# Main_and_Tower.net
KiCad netlist of a schematic drawn in EAGLE
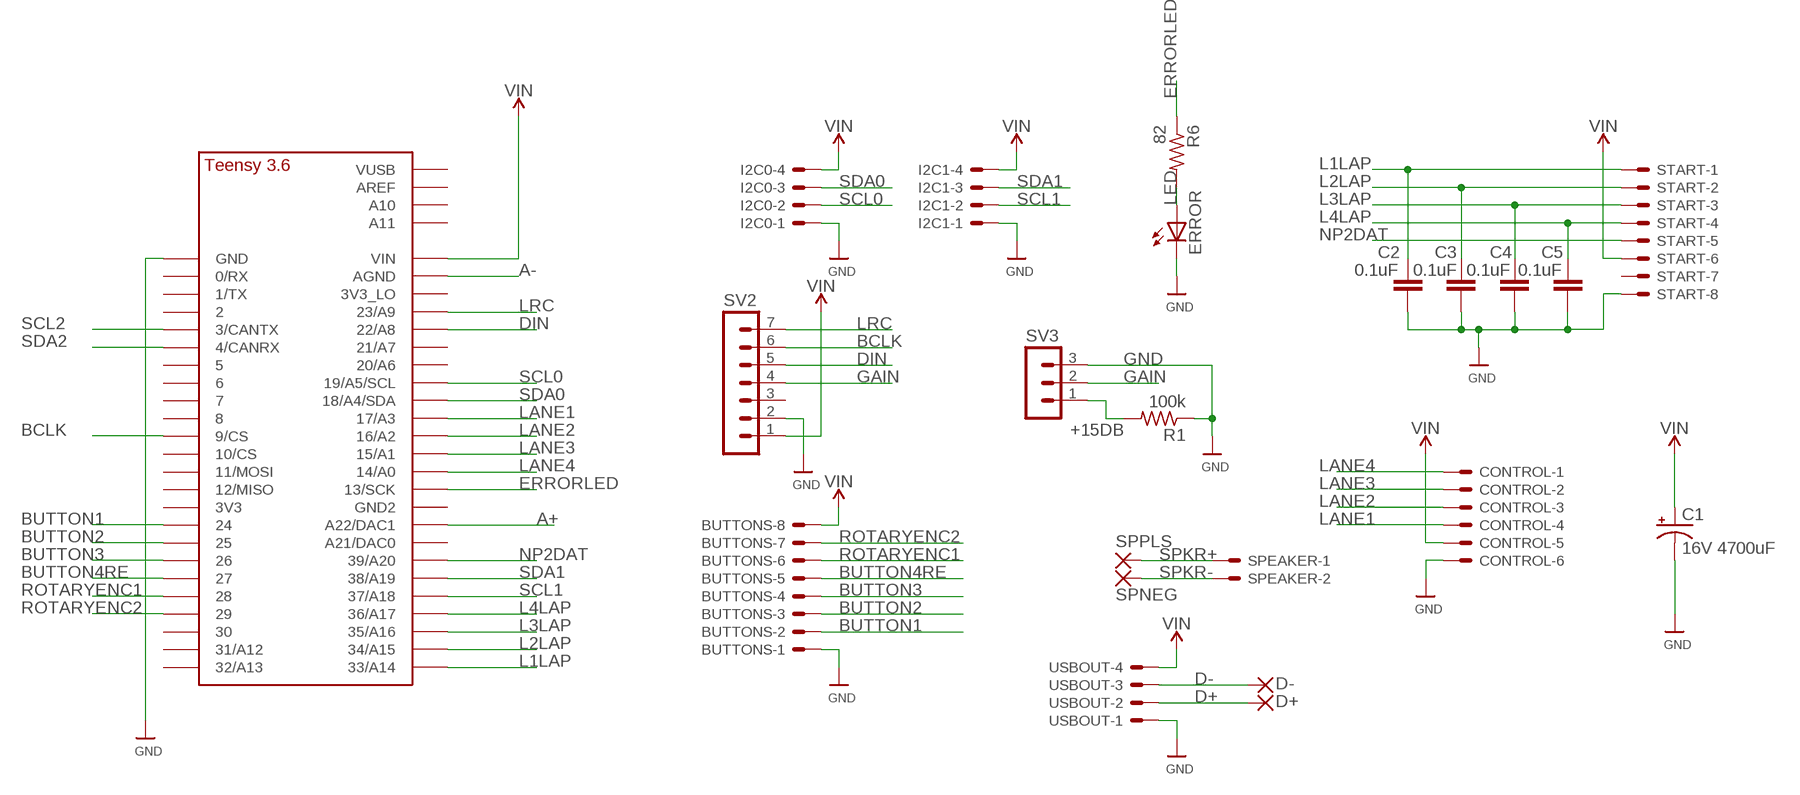
[diagram p0: schematic, sheet 1]

(export (version "E")
  (design (tool "Eeschema 10.0.6"))
  (components
    (comp (ref "BUTTONS")
      (value "KK-156-8")
      (footprint "eagle-import:KK-156-8")
      (fields (field (name "MF") "MOLEX"))
      (libsource (lib "eagle-import") (part "KK-156-8"))
    )
    (comp (ref "C1")
      (value "16V 4700uF")
      (footprint "eagle-import:CAPPRD550W110D1250H2500B")
      (libsource (lib "eagle-import") (part "C-POL-USRADIAL-25MM-DIA_"))
    )
    (comp (ref "C2")
      (value "0.1uF")
      (footprint "eagle-import:CAPC3216X135")
      (libsource (lib "eagle-import") (part "CCHIP-1206(3216-METRIC)_"))
    )
    (comp (ref "C3")
      (value "0.1uF")
      (footprint "eagle-import:CAPC3216X135")
      (libsource (lib "eagle-import") (part "CCHIP-1206(3216-METRIC)_"))
    )
    (comp (ref "C4")
      (value "0.1uF")
      (footprint "eagle-import:CAPC3216X135")
      (libsource (lib "eagle-import") (part "CCHIP-1206(3216-METRIC)_"))
    )
    (comp (ref "C5")
      (value "0.1uF")
      (footprint "eagle-import:CAPC3216X135")
      (libsource (lib "eagle-import") (part "CCHIP-1206(3216-METRIC)_"))
    )
    (comp (ref "CONTROL")
      (value "KK-156-6")
      (footprint "eagle-import:KK-156-6")
      (fields (field (name "MF") "MOLEX"))
      (libsource (lib "eagle-import") (part "KK-156-6"))
    )
    (comp (ref "D+")
      (value "1,6/0,8")
      (footprint "eagle-import:1,6_0,8")
      (libsource (lib "eagle-import") (part "1,6/0,8"))
    )
    (comp (ref "D-")
      (value "1,6/0,8")
      (footprint "eagle-import:1,6_0,8")
      (libsource (lib "eagle-import") (part "1,6/0,8"))
    )
    (comp (ref "ERROR")
      (value "LEDCHIPLED_1206")
      (footprint "eagle-import:CHIPLED_1206")
      (libsource (lib "eagle-import") (part "LEDCHIPLED_1206"))
    )
    (comp (ref "I2C0")
      (value "KK-156-4")
      (footprint "eagle-import:KK-156-4")
      (fields (field (name "MF") "MOLEX"))
      (libsource (lib "eagle-import") (part "KK-156-4"))
    )
    (comp (ref "I2C1")
      (value "KK-156-4")
      (footprint "eagle-import:KK-156-4")
      (fields (field (name "MF") "MOLEX"))
      (libsource (lib "eagle-import") (part "KK-156-4"))
    )
    (comp (ref "R1")
      (value "100k")
      (footprint "eagle-import:M1206")
      (libsource (lib "eagle-import") (part "R-US_M1206"))
    )
    (comp (ref "R6")
      (value "82")
      (footprint "eagle-import:M1206")
      (libsource (lib "eagle-import") (part "R-US_M1206"))
    )
    (comp (ref "SPEAKER")
      (value "KK-156-2")
      (footprint "eagle-import:KK-156-2")
      (fields (field (name "MF") "MOLEX"))
      (libsource (lib "eagle-import") (part "KK-156-2"))
    )
    (comp (ref "SPNEG")
      (value "2,54/1,1")
      (footprint "eagle-import:2,54_1,1")
      (libsource (lib "eagle-import") (part "2,54/1,1"))
    )
    (comp (ref "SPPLS")
      (value "2,54/1,1")
      (footprint "eagle-import:2,54_1,1")
      (libsource (lib "eagle-import") (part "2,54/1,1"))
    )
    (comp (ref "START")
      (value "KK-156-8")
      (footprint "eagle-import:KK-156-8")
      (fields (field (name "MF") "MOLEX"))
      (libsource (lib "eagle-import") (part "KK-156-8"))
    )
    (comp (ref "SV2")
      (value "MA07-1")
      (footprint "eagle-import:MA07-1")
      (libsource (lib "eagle-import") (part "MA07-1"))
    )
    (comp (ref "SV3")
      (value "MA03-1")
      (footprint "eagle-import:MA03-1")
      (libsource (lib "eagle-import") (part "MA03-1"))
    )
    (comp (ref "U$1")
      (value "TEENSY_3.5/3.6_BASIC")
      (footprint "eagle-import:TEENSY_3.5_3.6_BASIC")
      (libsource (lib "eagle-import") (part "TEENSY_3.5/3.6_BASIC"))
    )
    (comp (ref "USBOUT")
      (value "KK-156-4")
      (footprint "eagle-import:KK-156-4")
      (fields (field (name "MF") "MOLEX"))
      (libsource (lib "eagle-import") (part "KK-156-4"))
    )
  )
  (nets
    (net (code "1") (name "/+15DB") (class "Default")
      (node (ref "R1") (pin "2") (pinfunction "2_2") (pintype "passive"))
      (node (ref "SV3") (pin "1") (pinfunction "1_1") (pintype "passive"))
    )
    (net (code "2") (name "/A+") (class "Default")
      (node (ref "U$1") (pin "A22/DAC1") (pinfunction "A22/DAC1_A22/DAC1") (pintype "bidirectional"))
    )
    (net (code "3") (name "/A-") (class "Default")
      (node (ref "U$1") (pin "AGND") (pinfunction "AGND_AGND") (pintype "bidirectional"))
    )
    (net (code "4") (name "/BCLK") (class "Default")
      (node (ref "SV2") (pin "6") (pinfunction "6_6") (pintype "passive"))
      (node (ref "U$1") (pin "9/CS") (pinfunction "9/CS_9/CS") (pintype "bidirectional"))
    )
    (net (code "5") (name "/BUTTON1") (class "Default")
      (node (ref "BUTTONS") (pin "2") (pinfunction "S_2") (pintype "passive"))
      (node (ref "U$1") (pin "24") (pinfunction "24_24") (pintype "bidirectional"))
    )
    (net (code "6") (name "/BUTTON2") (class "Default")
      (node (ref "BUTTONS") (pin "3") (pinfunction "S_3") (pintype "passive"))
      (node (ref "U$1") (pin "25") (pinfunction "25_25") (pintype "bidirectional"))
    )
    (net (code "7") (name "/BUTTON3") (class "Default")
      (node (ref "BUTTONS") (pin "4") (pinfunction "S_4") (pintype "passive"))
      (node (ref "U$1") (pin "26") (pinfunction "26_26") (pintype "bidirectional"))
    )
    (net (code "8") (name "/BUTTON4RE") (class "Default")
      (node (ref "BUTTONS") (pin "5") (pinfunction "S_5") (pintype "passive"))
      (node (ref "U$1") (pin "27") (pinfunction "27_27") (pintype "bidirectional"))
    )
    (net (code "9") (name "/D+") (class "Default")
      (node (ref "D+") (pin "1") (pinfunction "P_1") (pintype "passive"))
      (node (ref "USBOUT") (pin "2") (pinfunction "S_2") (pintype "passive"))
    )
    (net (code "10") (name "/D-") (class "Default")
      (node (ref "D-") (pin "1") (pinfunction "P_1") (pintype "passive"))
      (node (ref "USBOUT") (pin "3") (pinfunction "S_3") (pintype "passive"))
    )
    (net (code "11") (name "/DIN") (class "Default")
      (node (ref "SV2") (pin "5") (pinfunction "5_5") (pintype "passive"))
      (node (ref "U$1") (pin "22/A8") (pinfunction "22/A8_22/A8") (pintype "bidirectional"))
    )
    (net (code "12") (name "/ERRORLED") (class "Default")
      (node (ref "R6") (pin "1") (pinfunction "1_1") (pintype "passive"))
      (node (ref "U$1") (pin "13/SCK") (pinfunction "13/SCK_13/SCK") (pintype "bidirectional"))
    )
    (net (code "13") (name "/GAIN") (class "Default")
      (node (ref "SV2") (pin "4") (pinfunction "4_4") (pintype "passive"))
      (node (ref "SV3") (pin "2") (pinfunction "2_2") (pintype "passive"))
    )
    (net (code "14") (name "/L1LAP") (class "Default")
      (node (ref "C2") (pin "1") (pinfunction "1_1") (pintype "passive"))
      (node (ref "START") (pin "1") (pinfunction "S_1") (pintype "passive"))
      (node (ref "U$1") (pin "33/A14") (pinfunction "33/A14_33/A14") (pintype "bidirectional"))
    )
    (net (code "15") (name "/L2LAP") (class "Default")
      (node (ref "C3") (pin "1") (pinfunction "1_1") (pintype "passive"))
      (node (ref "START") (pin "2") (pinfunction "S_2") (pintype "passive"))
      (node (ref "U$1") (pin "34/A15") (pinfunction "34/A15_34/A15") (pintype "bidirectional"))
    )
    (net (code "16") (name "/L3LAP") (class "Default")
      (node (ref "C4") (pin "1") (pinfunction "1_1") (pintype "passive"))
      (node (ref "START") (pin "3") (pinfunction "S_3") (pintype "passive"))
      (node (ref "U$1") (pin "35/A16") (pinfunction "35/A16_35/A16") (pintype "bidirectional"))
    )
    (net (code "17") (name "/L4LAP") (class "Default")
      (node (ref "C5") (pin "1") (pinfunction "1_1") (pintype "passive"))
      (node (ref "START") (pin "4") (pinfunction "S_4") (pintype "passive"))
      (node (ref "U$1") (pin "36/A17") (pinfunction "36/A17_36/A17") (pintype "bidirectional"))
    )
    (net (code "18") (name "/LANE1") (class "Default")
      (node (ref "CONTROL") (pin "4") (pinfunction "S_4") (pintype "passive"))
      (node (ref "U$1") (pin "17/A3") (pinfunction "17/A3_17/A3") (pintype "bidirectional"))
    )
    (net (code "19") (name "/LANE2") (class "Default")
      (node (ref "CONTROL") (pin "3") (pinfunction "S_3") (pintype "passive"))
      (node (ref "U$1") (pin "16/A2") (pinfunction "16/A2_16/A2") (pintype "bidirectional"))
    )
    (net (code "20") (name "/LANE3") (class "Default")
      (node (ref "CONTROL") (pin "2") (pinfunction "S_2") (pintype "passive"))
      (node (ref "U$1") (pin "15/A1") (pinfunction "15/A1_15/A1") (pintype "bidirectional"))
    )
    (net (code "21") (name "/LANE4") (class "Default")
      (node (ref "CONTROL") (pin "1") (pinfunction "S_1") (pintype "passive"))
      (node (ref "U$1") (pin "14/A0") (pinfunction "14/A0_14/A0") (pintype "bidirectional"))
    )
    (net (code "22") (name "/LED") (class "Default")
      (node (ref "ERROR") (pin "A") (pinfunction "A_A") (pintype "passive"))
      (node (ref "R6") (pin "2") (pinfunction "2_2") (pintype "passive"))
    )
    (net (code "23") (name "/LRC") (class "Default")
      (node (ref "SV2") (pin "7") (pinfunction "7_7") (pintype "passive"))
      (node (ref "U$1") (pin "23/A9") (pinfunction "23/A9_23/A9") (pintype "bidirectional"))
    )
    (net (code "24") (name "/NP2DAT") (class "Default")
      (node (ref "START") (pin "5") (pinfunction "S_5") (pintype "passive"))
      (node (ref "U$1") (pin "39/A20") (pinfunction "39/A20_39/A20") (pintype "bidirectional"))
    )
    (net (code "25") (name "/ROTARYENC1") (class "Default")
      (node (ref "BUTTONS") (pin "6") (pinfunction "S_6") (pintype "passive"))
      (node (ref "U$1") (pin "28") (pinfunction "28_28") (pintype "bidirectional"))
    )
    (net (code "26") (name "/ROTARYENC2") (class "Default")
      (node (ref "BUTTONS") (pin "7") (pinfunction "S_7") (pintype "passive"))
      (node (ref "U$1") (pin "29") (pinfunction "29_29") (pintype "bidirectional"))
    )
    (net (code "27") (name "/SCL0") (class "Default")
      (node (ref "I2C0") (pin "2") (pinfunction "S_2") (pintype "passive"))
      (node (ref "U$1") (pin "19/A5/SCL") (pinfunction "19/A5/SCL_19/A5/SCL") (pintype "bidirectional"))
    )
    (net (code "28") (name "/SCL1") (class "Default")
      (node (ref "I2C1") (pin "2") (pinfunction "S_2") (pintype "passive"))
      (node (ref "U$1") (pin "37/A18") (pinfunction "37/A18_37/A18") (pintype "bidirectional"))
    )
    (net (code "29") (name "/SCL2") (class "Default")
      (node (ref "U$1") (pin "3/CANTX") (pinfunction "3/CANTX_3/CANTX") (pintype "bidirectional"))
    )
    (net (code "30") (name "/SDA0") (class "Default")
      (node (ref "I2C0") (pin "3") (pinfunction "S_3") (pintype "passive"))
      (node (ref "U$1") (pin "18/A4/SDA") (pinfunction "18/A4/SDA_18/A4/SDA") (pintype "bidirectional"))
    )
    (net (code "31") (name "/SDA1") (class "Default")
      (node (ref "I2C1") (pin "3") (pinfunction "S_3") (pintype "passive"))
      (node (ref "U$1") (pin "38/A19") (pinfunction "38/A19_38/A19") (pintype "bidirectional"))
    )
    (net (code "32") (name "/SDA2") (class "Default")
      (node (ref "U$1") (pin "4/CANRX") (pinfunction "4/CANRX_4/CANRX") (pintype "bidirectional"))
    )
    (net (code "33") (name "/SPKR+") (class "Default")
      (node (ref "SPEAKER") (pin "1") (pinfunction "S_1") (pintype "passive"))
      (node (ref "SPPLS") (pin "1") (pinfunction "P_1") (pintype "passive"))
    )
    (net (code "34") (name "/SPKR-") (class "Default")
      (node (ref "SPEAKER") (pin "2") (pinfunction "S_2") (pintype "passive"))
      (node (ref "SPNEG") (pin "1") (pinfunction "P_1") (pintype "passive"))
    )
    (net (code "35") (name "GND") (class "Default")
      (node (ref "BUTTONS") (pin "1") (pinfunction "S_1") (pintype "passive"))
      (node (ref "C1") (pin "2") (pinfunction "-_2") (pintype "passive"))
      (node (ref "C2") (pin "2") (pinfunction "2_2") (pintype "passive"))
      (node (ref "C3") (pin "2") (pinfunction "2_2") (pintype "passive"))
      (node (ref "C4") (pin "2") (pinfunction "2_2") (pintype "passive"))
      (node (ref "C5") (pin "2") (pinfunction "2_2") (pintype "passive"))
      (node (ref "CONTROL") (pin "6") (pinfunction "S_6") (pintype "passive"))
      (node (ref "ERROR") (pin "C") (pinfunction "C_C") (pintype "passive"))
      (node (ref "I2C0") (pin "1") (pinfunction "S_1") (pintype "passive"))
      (node (ref "I2C1") (pin "1") (pinfunction "S_1") (pintype "passive"))
      (node (ref "R1") (pin "1") (pinfunction "1_1") (pintype "passive"))
      (node (ref "START") (pin "8") (pinfunction "S_8") (pintype "passive"))
      (node (ref "SV2") (pin "2") (pinfunction "2_2") (pintype "passive"))
      (node (ref "SV3") (pin "3") (pinfunction "3_3") (pintype "passive"))
      (node (ref "U$1") (pin "GND") (pinfunction "GND_GND") (pintype "bidirectional"))
      (node (ref "USBOUT") (pin "1") (pinfunction "S_1") (pintype "passive"))
    )
    (net (code "36") (name "VIN") (class "Default")
      (node (ref "BUTTONS") (pin "8") (pinfunction "S_8") (pintype "passive"))
      (node (ref "C1") (pin "1") (pinfunction "+_1") (pintype "passive"))
      (node (ref "CONTROL") (pin "5") (pinfunction "S_5") (pintype "passive"))
      (node (ref "I2C0") (pin "4") (pinfunction "S_4") (pintype "passive"))
      (node (ref "I2C1") (pin "4") (pinfunction "S_4") (pintype "passive"))
      (node (ref "START") (pin "6") (pinfunction "S_6") (pintype "passive"))
      (node (ref "SV2") (pin "1") (pinfunction "1_1") (pintype "passive"))
      (node (ref "U$1") (pin "VIN") (pinfunction "VIN_VIN") (pintype "bidirectional"))
      (node (ref "USBOUT") (pin "4") (pinfunction "S_4") (pintype "passive"))
    )
    (net (code "37") (name "unconnected-(STARTG-S-Pad7)") (class "Default")
      (node (ref "START") (pin "7") (pinfunction "S_7") (pintype "passive"))
    )
    (net (code "38") (name "unconnected-(SV2-Pad3)") (class "Default")
      (node (ref "SV2") (pin "3") (pinfunction "3_3") (pintype "passive"))
    )
    (net (code "39") (name "unconnected-(U$1-A21{slash}DAC0-Pad21{slash}DAC0)") (class "Default")
      (node (ref "U$1") (pin "21/DAC0") (pinfunction "A21/DAC0_21/DAC0") (pintype "bidirectional"))
    )
    (net (code "40") (name "unconnected-(U$1-Pad0{slash}RX)") (class "Default")
      (node (ref "U$1") (pin "0/RX") (pinfunction "0/RX_0/RX") (pintype "bidirectional"))
    )
    (net (code "41") (name "unconnected-(U$1-Pad1{slash}TX)") (class "Default")
      (node (ref "U$1") (pin "1/TX") (pinfunction "1/TX_1/TX") (pintype "bidirectional"))
    )
    (net (code "42") (name "unconnected-(U$1-Pad2)") (class "Default")
      (node (ref "U$1") (pin "2") (pinfunction "2_2") (pintype "bidirectional"))
    )
    (net (code "43") (name "unconnected-(U$1-Pad3V3)") (class "Default")
      (node (ref "U$1") (pin "3V3") (pinfunction "3V3_3V3") (pintype "bidirectional"))
    )
    (net (code "44") (name "unconnected-(U$1-Pad3V3_LO)") (class "Default")
      (node (ref "U$1") (pin "3V3_LO") (pinfunction "3V3_LO_3V3_LO") (pintype "bidirectional"))
    )
    (net (code "45") (name "unconnected-(U$1-Pad5)") (class "Default")
      (node (ref "U$1") (pin "5") (pinfunction "5_5") (pintype "bidirectional"))
    )
    (net (code "46") (name "unconnected-(U$1-Pad6)") (class "Default")
      (node (ref "U$1") (pin "6") (pinfunction "6_6") (pintype "bidirectional"))
    )
    (net (code "47") (name "unconnected-(U$1-Pad7)") (class "Default")
      (node (ref "U$1") (pin "7") (pinfunction "7_7") (pintype "bidirectional"))
    )
    (net (code "48") (name "unconnected-(U$1-Pad8)") (class "Default")
      (node (ref "U$1") (pin "8") (pinfunction "8_8") (pintype "bidirectional"))
    )
    (net (code "49") (name "unconnected-(U$1-Pad10{slash}CS)") (class "Default")
      (node (ref "U$1") (pin "10/CS") (pinfunction "10/CS_10/CS") (pintype "bidirectional"))
    )
    (net (code "50") (name "unconnected-(U$1-Pad11{slash}MOSI)") (class "Default")
      (node (ref "U$1") (pin "11/MOSI") (pinfunction "11/MOSI_11/MOSI") (pintype "bidirectional"))
    )
    (net (code "51") (name "unconnected-(U$1-Pad12{slash}MISO)") (class "Default")
      (node (ref "U$1") (pin "12/MISO") (pinfunction "12/MISO_12/MISO") (pintype "bidirectional"))
    )
    (net (code "52") (name "unconnected-(U$1-Pad20{slash}A6)") (class "Default")
      (node (ref "U$1") (pin "20/A6") (pinfunction "20/A6_20/A6") (pintype "bidirectional"))
    )
    (net (code "53") (name "unconnected-(U$1-Pad21{slash}A7)") (class "Default")
      (node (ref "U$1") (pin "21/A7") (pinfunction "21/A7_21/A7") (pintype "bidirectional"))
    )
    (net (code "54") (name "unconnected-(U$1-Pad30)") (class "Default")
      (node (ref "U$1") (pin "30") (pinfunction "30_30") (pintype "bidirectional"))
    )
    (net (code "55") (name "unconnected-(U$1-Pad31{slash}A12)") (class "Default")
      (node (ref "U$1") (pin "31/A12") (pinfunction "31/A12_31/A12") (pintype "bidirectional"))
    )
    (net (code "56") (name "unconnected-(U$1-Pad32{slash}A13)") (class "Default")
      (node (ref "U$1") (pin "32/A13") (pinfunction "32/A13_32/A13") (pintype "bidirectional"))
    )
    (net (code "57") (name "unconnected-(U$1-PadA10)") (class "Default")
      (node (ref "U$1") (pin "A10") (pinfunction "A10_A10") (pintype "bidirectional"))
    )
    (net (code "58") (name "unconnected-(U$1-PadA11)") (class "Default")
      (node (ref "U$1") (pin "A11") (pinfunction "A11_A11") (pintype "bidirectional"))
    )
    (net (code "59") (name "unconnected-(U$1-PadAREF)") (class "Default")
      (node (ref "U$1") (pin "AREF") (pinfunction "AREF_AREF") (pintype "bidirectional"))
    )
    (net (code "60") (name "unconnected-(U$1-PadGND2)") (class "Default")
      (node (ref "U$1") (pin "GND2") (pinfunction "GND2_GND2") (pintype "bidirectional"))
    )
    (net (code "61") (name "unconnected-(U$1-PadVUSB)") (class "Default")
      (node (ref "U$1") (pin "VUSB") (pinfunction "VUSB_VUSB") (pintype "bidirectional"))
    )
  )
)
